# light.net
KiCad netlist of a schematic drawn in Altium Designer
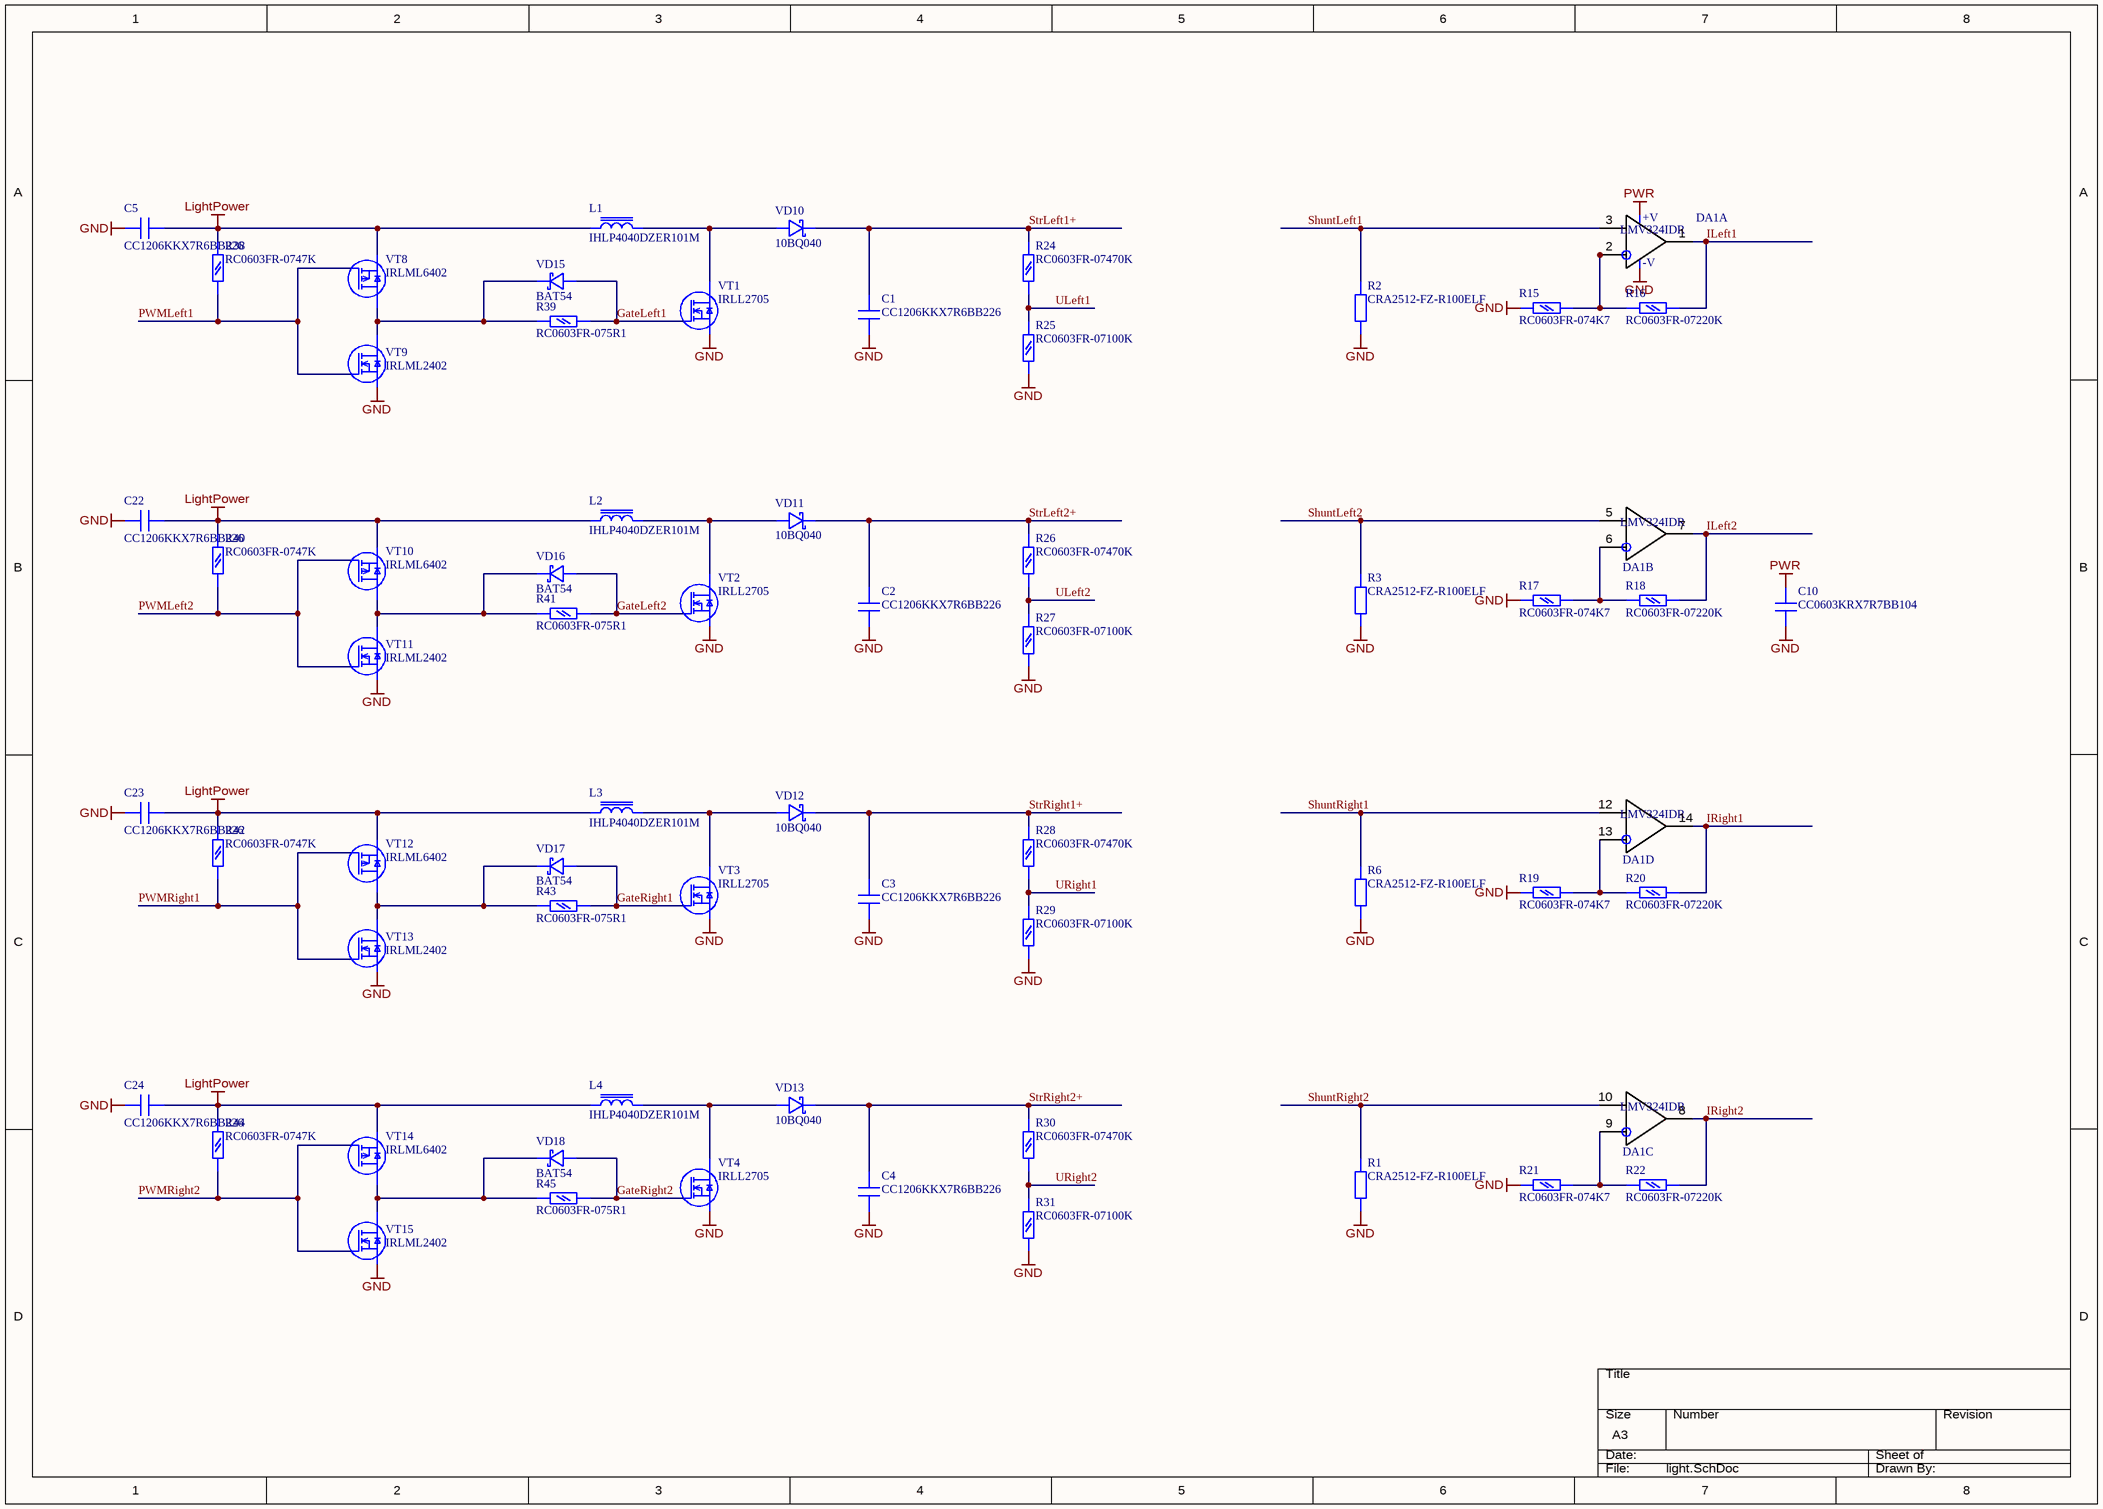
[diagram p0: light.SchDoc]

(export (version "E")
  (design (tool "Eeschema 10.0.6"))
  (components
    (comp (ref "C1")
      (value "CC1206KKX7R6BB226")
      (footprint "CapacitorSMD1206(reflow)")
      (description "CAPACITOR Capacitor SMD 1206 3.2x1.6mm")
      (libsource (lib "Integrated_Library") (part "CapacitorSMD1206(reflow)"))
    )
    (comp (ref "C2")
      (value "CC1206KKX7R6BB226")
      (footprint "CapacitorSMD1206(reflow)")
      (description "CAPACITOR Capacitor SMD 1206 3.2x1.6mm")
      (libsource (lib "Integrated_Library") (part "CapacitorSMD1206(reflow)"))
    )
    (comp (ref "C3")
      (value "CC1206KKX7R6BB226")
      (footprint "CapacitorSMD1206(reflow)")
      (description "CAPACITOR Capacitor SMD 1206 3.2x1.6mm")
      (libsource (lib "Integrated_Library") (part "CapacitorSMD1206(reflow)"))
    )
    (comp (ref "C4")
      (value "CC1206KKX7R6BB226")
      (footprint "CapacitorSMD1206(reflow)")
      (description "CAPACITOR Capacitor SMD 1206 3.2x1.6mm")
      (libsource (lib "Integrated_Library") (part "CapacitorSMD1206(reflow)"))
    )
    (comp (ref "C5")
      (value "CC1206KKX7R6BB226")
      (footprint "CapacitorSMD1206(reflow)")
      (description "CAPACITOR Capacitor SMD 1206 3.2x1.6mm")
      (libsource (lib "Integrated_Library") (part "CapacitorSMD1206(reflow)"))
    )
    (comp (ref "C10")
      (value "CC0603KRX7R7BB104")
      (footprint "CapacitorSMD0603(manual)")
      (description "CAPACITOR Capacitor SMD 0603 1.6x0.8mm")
      (libsource (lib "Integrated_Library") (part "CapacitorSMD0603(reflow)"))
    )
    (comp (ref "C22")
      (value "CC1206KKX7R6BB226")
      (footprint "CapacitorSMD1206(reflow)")
      (description "CAPACITOR Capacitor SMD 1206 3.2x1.6mm")
      (libsource (lib "Integrated_Library") (part "CapacitorSMD1206(reflow)"))
    )
    (comp (ref "C23")
      (value "CC1206KKX7R6BB226")
      (footprint "CapacitorSMD1206(reflow)")
      (description "CAPACITOR Capacitor SMD 1206 3.2x1.6mm")
      (libsource (lib "Integrated_Library") (part "CapacitorSMD1206(reflow)"))
    )
    (comp (ref "C24")
      (value "CC1206KKX7R6BB226")
      (footprint "CapacitorSMD1206(reflow)")
      (description "CAPACITOR Capacitor SMD 1206 3.2x1.6mm")
      (libsource (lib "Integrated_Library") (part "CapacitorSMD1206(reflow)"))
    )
    (comp (ref "DA1")
      (value "LMV324IDR")
      (footprint "SO14")
      (description "IC generic quad op amp SO14")
      (libsource (lib "Integrated_Library") (part "OpAmp_Quad_SO14"))
    )
    (comp (ref "L1")
      (value "IHLP4040DZER101M")
      (footprint "IHLP-4040DZ(manual/deep1.5mm)")
      (description "MAGNETIC Inductor SMD 4040 h=4mm")
      (libsource (lib "Integrated_Library") (part "IHLP-4040DZ"))
    )
    (comp (ref "L2")
      (value "IHLP4040DZER101M")
      (footprint "IHLP-4040DZ(manual/deep1.5mm)")
      (description "MAGNETIC Inductor SMD 4040 h=4mm")
      (libsource (lib "Integrated_Library") (part "IHLP-4040DZ"))
    )
    (comp (ref "L3")
      (value "IHLP4040DZER101M")
      (footprint "IHLP-4040DZ(manual/deep1.5mm)")
      (description "MAGNETIC Inductor SMD 4040 h=4mm")
      (libsource (lib "Integrated_Library") (part "IHLP-4040DZ"))
    )
    (comp (ref "L4")
      (value "IHLP4040DZER101M")
      (footprint "IHLP-4040DZ(manual/deep1.5mm)")
      (description "MAGNETIC Inductor SMD 4040 h=4mm")
      (libsource (lib "Integrated_Library") (part "IHLP-4040DZ"))
    )
    (comp (ref "R1")
      (value "CRA2512-FZ-R100ELF")
      (footprint "ResistorSMD2512(reflow)")
      (description "RESISTOR Resistor SMD 2512 6.35x3.2mm")
      (libsource (lib "Integrated_Library") (part "ResistorSMD2512(reflow)"))
    )
    (comp (ref "R2")
      (value "CRA2512-FZ-R100ELF")
      (footprint "ResistorSMD2512(reflow)")
      (description "RESISTOR Resistor SMD 2512 6.35x3.2mm")
      (libsource (lib "Integrated_Library") (part "ResistorSMD2512(reflow)"))
    )
    (comp (ref "R3")
      (value "CRA2512-FZ-R100ELF")
      (footprint "ResistorSMD2512(reflow)")
      (description "RESISTOR Resistor SMD 2512 6.35x3.2mm")
      (libsource (lib "Integrated_Library") (part "ResistorSMD2512(reflow)"))
    )
    (comp (ref "R6")
      (value "CRA2512-FZ-R100ELF")
      (footprint "ResistorSMD2512(reflow)")
      (description "RESISTOR Resistor SMD 2512 6.35x3.2mm")
      (libsource (lib "Integrated_Library") (part "ResistorSMD2512(reflow)"))
    )
    (comp (ref "R15")
      (value "RC0603FR-074K7")
      (footprint "ResistorSMD0603(manual)")
      (description "RESISTOR Resistor SMD 0603 1.6x0.8mm")
      (libsource (lib "Integrated_Library") (part "ResistorSMD0603(reflow)"))
    )
    (comp (ref "R16")
      (value "RC0603FR-07220K")
      (footprint "ResistorSMD0603(manual)")
      (description "RESISTOR Resistor SMD 0603 1.6x0.8mm")
      (libsource (lib "Integrated_Library") (part "ResistorSMD0603(reflow)"))
    )
    (comp (ref "R17")
      (value "RC0603FR-074K7")
      (footprint "ResistorSMD0603(manual)")
      (description "RESISTOR Resistor SMD 0603 1.6x0.8mm")
      (libsource (lib "Integrated_Library") (part "ResistorSMD0603(reflow)"))
    )
    (comp (ref "R18")
      (value "RC0603FR-07220K")
      (footprint "ResistorSMD0603(manual)")
      (description "RESISTOR Resistor SMD 0603 1.6x0.8mm")
      (libsource (lib "Integrated_Library") (part "ResistorSMD0603(reflow)"))
    )
    (comp (ref "R19")
      (value "RC0603FR-074K7")
      (footprint "ResistorSMD0603(manual)")
      (description "RESISTOR Resistor SMD 0603 1.6x0.8mm")
      (libsource (lib "Integrated_Library") (part "ResistorSMD0603(reflow)"))
    )
    (comp (ref "R20")
      (value "RC0603FR-07220K")
      (footprint "ResistorSMD0603(manual)")
      (description "RESISTOR Resistor SMD 0603 1.6x0.8mm")
      (libsource (lib "Integrated_Library") (part "ResistorSMD0603(reflow)"))
    )
    (comp (ref "R21")
      (value "RC0603FR-074K7")
      (footprint "ResistorSMD0603(manual)")
      (description "RESISTOR Resistor SMD 0603 1.6x0.8mm")
      (libsource (lib "Integrated_Library") (part "ResistorSMD0603(reflow)"))
    )
    (comp (ref "R22")
      (value "RC0603FR-07220K")
      (footprint "ResistorSMD0603(manual)")
      (description "RESISTOR Resistor SMD 0603 1.6x0.8mm")
      (libsource (lib "Integrated_Library") (part "ResistorSMD0603(reflow)"))
    )
    (comp (ref "R24")
      (value "RC0603FR-07470K")
      (footprint "ResistorSMD0603(manual)")
      (description "RESISTOR Resistor SMD 0603 1.6x0.8mm")
      (libsource (lib "Integrated_Library") (part "ResistorSMD0603(reflow)"))
    )
    (comp (ref "R25")
      (value "RC0603FR-07100K")
      (footprint "ResistorSMD0603(manual)")
      (description "RESISTOR Resistor SMD 0603 1.6x0.8mm")
      (libsource (lib "Integrated_Library") (part "ResistorSMD0603(reflow)"))
    )
    (comp (ref "R26")
      (value "RC0603FR-07470K")
      (footprint "ResistorSMD0603(manual)")
      (description "RESISTOR Resistor SMD 0603 1.6x0.8mm")
      (libsource (lib "Integrated_Library") (part "ResistorSMD0603(reflow)"))
    )
    (comp (ref "R27")
      (value "RC0603FR-07100K")
      (footprint "ResistorSMD0603(manual)")
      (description "RESISTOR Resistor SMD 0603 1.6x0.8mm")
      (libsource (lib "Integrated_Library") (part "ResistorSMD0603(reflow)"))
    )
    (comp (ref "R28")
      (value "RC0603FR-07470K")
      (footprint "ResistorSMD0603(manual)")
      (description "RESISTOR Resistor SMD 0603 1.6x0.8mm")
      (libsource (lib "Integrated_Library") (part "ResistorSMD0603(reflow)"))
    )
    (comp (ref "R29")
      (value "RC0603FR-07100K")
      (footprint "ResistorSMD0603(manual)")
      (description "RESISTOR Resistor SMD 0603 1.6x0.8mm")
      (libsource (lib "Integrated_Library") (part "ResistorSMD0603(reflow)"))
    )
    (comp (ref "R30")
      (value "RC0603FR-07470K")
      (footprint "ResistorSMD0603(manual)")
      (description "RESISTOR Resistor SMD 0603 1.6x0.8mm")
      (libsource (lib "Integrated_Library") (part "ResistorSMD0603(reflow)"))
    )
    (comp (ref "R31")
      (value "RC0603FR-07100K")
      (footprint "ResistorSMD0603(manual)")
      (description "RESISTOR Resistor SMD 0603 1.6x0.8mm")
      (libsource (lib "Integrated_Library") (part "ResistorSMD0603(reflow)"))
    )
    (comp (ref "R38")
      (value "RC0603FR-0747K")
      (footprint "ResistorSMD0603(manual)")
      (description "RESISTOR Resistor SMD 0603 1.6x0.8mm")
      (libsource (lib "Integrated_Library") (part "ResistorSMD0603(reflow)"))
    )
    (comp (ref "R39")
      (value "RC0603FR-075R1")
      (footprint "ResistorSMD0603(manual)")
      (description "RESISTOR Resistor SMD 0603 1.6x0.8mm")
      (libsource (lib "Integrated_Library") (part "ResistorSMD0603(reflow)"))
    )
    (comp (ref "R40")
      (value "RC0603FR-0747K")
      (footprint "ResistorSMD0603(manual)")
      (description "RESISTOR Resistor SMD 0603 1.6x0.8mm")
      (libsource (lib "Integrated_Library") (part "ResistorSMD0603(reflow)"))
    )
    (comp (ref "R41")
      (value "RC0603FR-075R1")
      (footprint "ResistorSMD0603(manual)")
      (description "RESISTOR Resistor SMD 0603 1.6x0.8mm")
      (libsource (lib "Integrated_Library") (part "ResistorSMD0603(reflow)"))
    )
    (comp (ref "R42")
      (value "RC0603FR-0747K")
      (footprint "ResistorSMD0603(manual)")
      (description "RESISTOR Resistor SMD 0603 1.6x0.8mm")
      (libsource (lib "Integrated_Library") (part "ResistorSMD0603(reflow)"))
    )
    (comp (ref "R43")
      (value "RC0603FR-075R1")
      (footprint "ResistorSMD0603(manual)")
      (description "RESISTOR Resistor SMD 0603 1.6x0.8mm")
      (libsource (lib "Integrated_Library") (part "ResistorSMD0603(reflow)"))
    )
    (comp (ref "R44")
      (value "RC0603FR-0747K")
      (footprint "ResistorSMD0603(manual)")
      (description "RESISTOR Resistor SMD 0603 1.6x0.8mm")
      (libsource (lib "Integrated_Library") (part "ResistorSMD0603(reflow)"))
    )
    (comp (ref "R45")
      (value "RC0603FR-075R1")
      (footprint "ResistorSMD0603(manual)")
      (description "RESISTOR Resistor SMD 0603 1.6x0.8mm")
      (libsource (lib "Integrated_Library") (part "ResistorSMD0603(reflow)"))
    )
    (comp (ref "VD10")
      (value "10BQ040")
      (footprint "SMB_10BQ40")
      (description "DIODE Schottky rectifier")
      (libsource (lib "Integrated_Library") (part "10BQ___"))
    )
    (comp (ref "VD11")
      (value "10BQ040")
      (footprint "SMB_10BQ40")
      (description "DIODE Schottky rectifier")
      (libsource (lib "Integrated_Library") (part "10BQ___"))
    )
    (comp (ref "VD12")
      (value "10BQ040")
      (footprint "SMB_10BQ40")
      (description "DIODE Schottky rectifier")
      (libsource (lib "Integrated_Library") (part "10BQ___"))
    )
    (comp (ref "VD13")
      (value "10BQ040")
      (footprint "SMB_10BQ40")
      (description "DIODE Schottky rectifier")
      (libsource (lib "Integrated_Library") (part "10BQ___"))
    )
    (comp (ref "VD15")
      (value "BAT54")
      (footprint "SOT23")
      (description "DIODE Schottky barrier diodes")
      (libsource (lib "Integrated_Library") (part "BAT54"))
    )
    (comp (ref "VD16")
      (value "BAT54")
      (footprint "SOT23")
      (description "DIODE Schottky barrier diodes")
      (libsource (lib "Integrated_Library") (part "BAT54"))
    )
    (comp (ref "VD17")
      (value "BAT54")
      (footprint "SOT23")
      (description "DIODE Schottky barrier diodes")
      (libsource (lib "Integrated_Library") (part "BAT54"))
    )
    (comp (ref "VD18")
      (value "BAT54")
      (footprint "SOT23")
      (description "DIODE Schottky barrier diodes")
      (libsource (lib "Integrated_Library") (part "BAT54"))
    )
    (comp (ref "VT1")
      (value "IRLL2705")
      (footprint "SOT223")
      (description "TRANSISTOR MOSFET N generic sot23")
      (libsource (lib "Integrated_Library") (part "MOSFET_N_SOT223"))
    )
    (comp (ref "VT2")
      (value "IRLL2705")
      (footprint "SOT223")
      (description "TRANSISTOR MOSFET N generic sot23")
      (libsource (lib "Integrated_Library") (part "MOSFET_N_SOT223"))
    )
    (comp (ref "VT3")
      (value "IRLL2705")
      (footprint "SOT223")
      (description "TRANSISTOR MOSFET N generic sot23")
      (libsource (lib "Integrated_Library") (part "MOSFET_N_SOT223"))
    )
    (comp (ref "VT4")
      (value "IRLL2705")
      (footprint "SOT223")
      (description "TRANSISTOR MOSFET N generic sot23")
      (libsource (lib "Integrated_Library") (part "MOSFET_N_SOT223"))
    )
    (comp (ref "VT8")
      (value "IRLML6402")
      (footprint "SOT23")
      (description "TRANSISTOR MOSFET P generic sot23")
      (libsource (lib "Integrated_Library") (part "MOSFET_P_sot23"))
    )
    (comp (ref "VT9")
      (value "IRLML2402")
      (footprint "SOT23")
      (description "TRANSISTOR MOSFET N generic sot23")
      (libsource (lib "Integrated_Library") (part "MOSFET_N_sot23"))
    )
    (comp (ref "VT10")
      (value "IRLML6402")
      (footprint "SOT23")
      (description "TRANSISTOR MOSFET P generic sot23")
      (libsource (lib "Integrated_Library") (part "MOSFET_P_sot23"))
    )
    (comp (ref "VT11")
      (value "IRLML2402")
      (footprint "SOT23")
      (description "TRANSISTOR MOSFET N generic sot23")
      (libsource (lib "Integrated_Library") (part "MOSFET_N_sot23"))
    )
    (comp (ref "VT12")
      (value "IRLML6402")
      (footprint "SOT23")
      (description "TRANSISTOR MOSFET P generic sot23")
      (libsource (lib "Integrated_Library") (part "MOSFET_P_sot23"))
    )
    (comp (ref "VT13")
      (value "IRLML2402")
      (footprint "SOT23")
      (description "TRANSISTOR MOSFET N generic sot23")
      (libsource (lib "Integrated_Library") (part "MOSFET_N_sot23"))
    )
    (comp (ref "VT14")
      (value "IRLML6402")
      (footprint "SOT23")
      (description "TRANSISTOR MOSFET P generic sot23")
      (libsource (lib "Integrated_Library") (part "MOSFET_P_sot23"))
    )
    (comp (ref "VT15")
      (value "IRLML2402")
      (footprint "SOT23")
      (description "TRANSISTOR MOSFET N generic sot23")
      (libsource (lib "Integrated_Library") (part "MOSFET_N_sot23"))
    )
  )
  (nets
    (net (code "1") (name "/GateLeft1") (class "Default")
      (node (ref "R39") (pin "1") (pinfunction "1_1") (pintype "passive"))
      (node (ref "VD15") (pin "1") (pintype "passive"))
      (node (ref "VT1") (pin "1") (pinfunction "G_1") (pintype "passive"))
    )
    (net (code "2") (name "/GateLeft2") (class "Default")
      (node (ref "R41") (pin "1") (pinfunction "1_1") (pintype "passive"))
      (node (ref "VD16") (pin "1") (pintype "passive"))
      (node (ref "VT2") (pin "1") (pinfunction "G_1") (pintype "passive"))
    )
    (net (code "3") (name "/GateRight1") (class "Default")
      (node (ref "R43") (pin "1") (pinfunction "1_1") (pintype "passive"))
      (node (ref "VD17") (pin "1") (pintype "passive"))
      (node (ref "VT3") (pin "1") (pinfunction "G_1") (pintype "passive"))
    )
    (net (code "4") (name "/GateRight2") (class "Default")
      (node (ref "R45") (pin "1") (pinfunction "1_1") (pintype "passive"))
      (node (ref "VD18") (pin "1") (pintype "passive"))
      (node (ref "VT4") (pin "1") (pinfunction "G_1") (pintype "passive"))
    )
    (net (code "5") (name "/ILeft1") (class "Default")
      (node (ref "DA1") (pin "1") (pinfunction "1_1") (pintype "passive"))
      (node (ref "R16") (pin "2") (pinfunction "2_2") (pintype "passive"))
    )
    (net (code "6") (name "/ILeft2") (class "Default")
      (node (ref "DA1") (pin "7") (pinfunction "7_7") (pintype "passive"))
      (node (ref "R18") (pin "2") (pinfunction "2_2") (pintype "passive"))
    )
    (net (code "7") (name "/IRight1") (class "Default")
      (node (ref "DA1") (pin "14") (pinfunction "14_14") (pintype "passive"))
      (node (ref "R20") (pin "2") (pinfunction "2_2") (pintype "passive"))
    )
    (net (code "8") (name "/IRight2") (class "Default")
      (node (ref "DA1") (pin "8") (pinfunction "8_8") (pintype "passive"))
      (node (ref "R22") (pin "2") (pinfunction "2_2") (pintype "passive"))
    )
    (net (code "9") (name "/PWMLeft1") (class "Default")
      (node (ref "R38") (pin "2") (pinfunction "2_2") (pintype "passive"))
      (node (ref "VT8") (pin "1") (pinfunction "G_1") (pintype "passive"))
      (node (ref "VT9") (pin "1") (pinfunction "G_1") (pintype "passive"))
    )
    (net (code "10") (name "/PWMLeft2") (class "Default")
      (node (ref "R40") (pin "2") (pinfunction "2_2") (pintype "passive"))
      (node (ref "VT10") (pin "1") (pinfunction "G_1") (pintype "passive"))
      (node (ref "VT11") (pin "1") (pinfunction "G_1") (pintype "passive"))
    )
    (net (code "11") (name "/PWMRight1") (class "Default")
      (node (ref "R42") (pin "2") (pinfunction "2_2") (pintype "passive"))
      (node (ref "VT12") (pin "1") (pinfunction "G_1") (pintype "passive"))
      (node (ref "VT13") (pin "1") (pinfunction "G_1") (pintype "passive"))
    )
    (net (code "12") (name "/PWMRight2") (class "Default")
      (node (ref "R44") (pin "2") (pinfunction "2_2") (pintype "passive"))
      (node (ref "VT14") (pin "1") (pinfunction "G_1") (pintype "passive"))
      (node (ref "VT15") (pin "1") (pinfunction "G_1") (pintype "passive"))
    )
    (net (code "13") (name "/ShuntLeft1") (class "Default")
      (node (ref "DA1") (pin "3") (pinfunction "3_3") (pintype "passive"))
      (node (ref "R2") (pin "2") (pinfunction "2_2") (pintype "passive"))
    )
    (net (code "14") (name "/ShuntLeft2") (class "Default")
      (node (ref "DA1") (pin "5") (pinfunction "5_5") (pintype "passive"))
      (node (ref "R3") (pin "2") (pinfunction "2_2") (pintype "passive"))
    )
    (net (code "15") (name "/ShuntRight1") (class "Default")
      (node (ref "DA1") (pin "12") (pinfunction "12_12") (pintype "passive"))
      (node (ref "R6") (pin "2") (pinfunction "2_2") (pintype "passive"))
    )
    (net (code "16") (name "/ShuntRight2") (class "Default")
      (node (ref "DA1") (pin "10") (pinfunction "10_10") (pintype "passive"))
      (node (ref "R1") (pin "2") (pinfunction "2_2") (pintype "passive"))
    )
    (net (code "17") (name "/StrLeft1+") (class "Default")
      (node (ref "C1") (pin "2") (pintype "passive"))
      (node (ref "R24") (pin "2") (pinfunction "2_2") (pintype "passive"))
      (node (ref "VD10") (pin "2") (pintype "passive"))
    )
    (net (code "18") (name "/StrLeft2+") (class "Default")
      (node (ref "C2") (pin "2") (pintype "passive"))
      (node (ref "R26") (pin "2") (pinfunction "2_2") (pintype "passive"))
      (node (ref "VD11") (pin "2") (pintype "passive"))
    )
    (net (code "19") (name "/StrRight1+") (class "Default")
      (node (ref "C3") (pin "2") (pintype "passive"))
      (node (ref "R28") (pin "2") (pinfunction "2_2") (pintype "passive"))
      (node (ref "VD12") (pin "2") (pintype "passive"))
    )
    (net (code "20") (name "/StrRight2+") (class "Default")
      (node (ref "C4") (pin "2") (pintype "passive"))
      (node (ref "R30") (pin "2") (pinfunction "2_2") (pintype "passive"))
      (node (ref "VD13") (pin "2") (pintype "passive"))
    )
    (net (code "21") (name "/ULeft1") (class "Default")
      (node (ref "R24") (pin "1") (pinfunction "1_1") (pintype "passive"))
      (node (ref "R25") (pin "2") (pinfunction "2_2") (pintype "passive"))
    )
    (net (code "22") (name "/ULeft2") (class "Default")
      (node (ref "R26") (pin "1") (pinfunction "1_1") (pintype "passive"))
      (node (ref "R27") (pin "2") (pinfunction "2_2") (pintype "passive"))
    )
    (net (code "23") (name "/URight1") (class "Default")
      (node (ref "R28") (pin "1") (pinfunction "1_1") (pintype "passive"))
      (node (ref "R29") (pin "2") (pinfunction "2_2") (pintype "passive"))
    )
    (net (code "24") (name "/URight2") (class "Default")
      (node (ref "R30") (pin "1") (pinfunction "1_1") (pintype "passive"))
      (node (ref "R31") (pin "2") (pinfunction "2_2") (pintype "passive"))
    )
    (net (code "25") (name "GND") (class "Default")
      (node (ref "C1") (pin "1") (pintype "passive"))
      (node (ref "C10") (pin "1") (pintype "passive"))
      (node (ref "C2") (pin "1") (pintype "passive"))
      (node (ref "C22") (pin "2") (pintype "passive"))
      (node (ref "C23") (pin "2") (pintype "passive"))
      (node (ref "C24") (pin "2") (pintype "passive"))
      (node (ref "C3") (pin "1") (pintype "passive"))
      (node (ref "C4") (pin "1") (pintype "passive"))
      (node (ref "C5") (pin "2") (pintype "passive"))
      (node (ref "DA1") (pin "11") (pinfunction "11_11") (pintype "passive"))
      (node (ref "R1") (pin "1") (pinfunction "1_1") (pintype "passive"))
      (node (ref "R15") (pin "1") (pinfunction "1_1") (pintype "passive"))
      (node (ref "R17") (pin "1") (pinfunction "1_1") (pintype "passive"))
      (node (ref "R19") (pin "1") (pinfunction "1_1") (pintype "passive"))
      (node (ref "R2") (pin "1") (pinfunction "1_1") (pintype "passive"))
      (node (ref "R21") (pin "1") (pinfunction "1_1") (pintype "passive"))
      (node (ref "R25") (pin "1") (pinfunction "1_1") (pintype "passive"))
      (node (ref "R27") (pin "1") (pinfunction "1_1") (pintype "passive"))
      (node (ref "R29") (pin "1") (pinfunction "1_1") (pintype "passive"))
      (node (ref "R3") (pin "1") (pinfunction "1_1") (pintype "passive"))
      (node (ref "R31") (pin "1") (pinfunction "1_1") (pintype "passive"))
      (node (ref "R6") (pin "1") (pinfunction "1_1") (pintype "passive"))
      (node (ref "VT1") (pin "3") (pinfunction "S_3") (pintype "passive"))
      (node (ref "VT11") (pin "2") (pinfunction "S_2") (pintype "passive"))
      (node (ref "VT13") (pin "2") (pinfunction "S_2") (pintype "passive"))
      (node (ref "VT15") (pin "2") (pinfunction "S_2") (pintype "passive"))
      (node (ref "VT2") (pin "3") (pinfunction "S_3") (pintype "passive"))
      (node (ref "VT3") (pin "3") (pinfunction "S_3") (pintype "passive"))
      (node (ref "VT4") (pin "3") (pinfunction "S_3") (pintype "passive"))
      (node (ref "VT9") (pin "2") (pinfunction "S_2") (pintype "passive"))
    )
    (net (code "26") (name "LightPower") (class "Default")
      (node (ref "C22") (pin "1") (pintype "passive"))
      (node (ref "C23") (pin "1") (pintype "passive"))
      (node (ref "C24") (pin "1") (pintype "passive"))
      (node (ref "C5") (pin "1") (pintype "passive"))
      (node (ref "L1") (pin "1") (pintype "passive"))
      (node (ref "L2") (pin "1") (pintype "passive"))
      (node (ref "L3") (pin "1") (pintype "passive"))
      (node (ref "L4") (pin "1") (pintype "passive"))
      (node (ref "R38") (pin "1") (pinfunction "1_1") (pintype "passive"))
      (node (ref "R40") (pin "1") (pinfunction "1_1") (pintype "passive"))
      (node (ref "R42") (pin "1") (pinfunction "1_1") (pintype "passive"))
      (node (ref "R44") (pin "1") (pinfunction "1_1") (pintype "passive"))
      (node (ref "VT10") (pin "2") (pinfunction "S_2") (pintype "passive"))
      (node (ref "VT12") (pin "2") (pinfunction "S_2") (pintype "passive"))
      (node (ref "VT14") (pin "2") (pinfunction "S_2") (pintype "passive"))
      (node (ref "VT8") (pin "2") (pinfunction "S_2") (pintype "passive"))
    )
    (net (code "27") (name "Net-(DA1-Pad2)") (class "Default")
      (node (ref "DA1") (pin "2") (pinfunction "2_2") (pintype "passive"))
      (node (ref "R15") (pin "2") (pinfunction "2_2") (pintype "passive"))
      (node (ref "R16") (pin "1") (pinfunction "1_1") (pintype "passive"))
    )
    (net (code "28") (name "Net-(DA1-Pad6)") (class "Default")
      (node (ref "DA1") (pin "6") (pinfunction "6_6") (pintype "passive"))
      (node (ref "R17") (pin "2") (pinfunction "2_2") (pintype "passive"))
      (node (ref "R18") (pin "1") (pinfunction "1_1") (pintype "passive"))
    )
    (net (code "29") (name "Net-(DA1-Pad9)") (class "Default")
      (node (ref "DA1") (pin "9") (pinfunction "9_9") (pintype "passive"))
      (node (ref "R21") (pin "2") (pinfunction "2_2") (pintype "passive"))
      (node (ref "R22") (pin "1") (pinfunction "1_1") (pintype "passive"))
    )
    (net (code "30") (name "Net-(DA1-Pad13)") (class "Default")
      (node (ref "DA1") (pin "13") (pinfunction "13_13") (pintype "passive"))
      (node (ref "R19") (pin "2") (pinfunction "2_2") (pintype "passive"))
      (node (ref "R20") (pin "1") (pinfunction "1_1") (pintype "passive"))
    )
    (net (code "31") (name "Net-(VT1-D)") (class "Default")
      (node (ref "L1") (pin "2") (pintype "passive"))
      (node (ref "VD10") (pin "1") (pintype "passive"))
      (node (ref "VT1") (pin "2") (pinfunction "D_2") (pintype "passive"))
    )
    (net (code "32") (name "Net-(VT2-D)") (class "Default")
      (node (ref "L2") (pin "2") (pintype "passive"))
      (node (ref "VD11") (pin "1") (pintype "passive"))
      (node (ref "VT2") (pin "2") (pinfunction "D_2") (pintype "passive"))
    )
    (net (code "33") (name "Net-(VT3-D)") (class "Default")
      (node (ref "L3") (pin "2") (pintype "passive"))
      (node (ref "VD12") (pin "1") (pintype "passive"))
      (node (ref "VT3") (pin "2") (pinfunction "D_2") (pintype "passive"))
    )
    (net (code "34") (name "Net-(VT4-D)") (class "Default")
      (node (ref "L4") (pin "2") (pintype "passive"))
      (node (ref "VD13") (pin "1") (pintype "passive"))
      (node (ref "VT4") (pin "2") (pinfunction "D_2") (pintype "passive"))
    )
    (net (code "35") (name "Net-(VT8-D)") (class "Default")
      (node (ref "R39") (pin "2") (pinfunction "2_2") (pintype "passive"))
      (node (ref "VD15") (pin "3") (pintype "passive"))
      (node (ref "VT8") (pin "3") (pinfunction "D_3") (pintype "passive"))
      (node (ref "VT9") (pin "3") (pinfunction "D_3") (pintype "passive"))
    )
    (net (code "36") (name "Net-(VT10-D)") (class "Default")
      (node (ref "R41") (pin "2") (pinfunction "2_2") (pintype "passive"))
      (node (ref "VD16") (pin "3") (pintype "passive"))
      (node (ref "VT10") (pin "3") (pinfunction "D_3") (pintype "passive"))
      (node (ref "VT11") (pin "3") (pinfunction "D_3") (pintype "passive"))
    )
    (net (code "37") (name "Net-(VT12-D)") (class "Default")
      (node (ref "R43") (pin "2") (pinfunction "2_2") (pintype "passive"))
      (node (ref "VD17") (pin "3") (pintype "passive"))
      (node (ref "VT12") (pin "3") (pinfunction "D_3") (pintype "passive"))
      (node (ref "VT13") (pin "3") (pinfunction "D_3") (pintype "passive"))
    )
    (net (code "38") (name "Net-(VT14-D)") (class "Default")
      (node (ref "R45") (pin "2") (pinfunction "2_2") (pintype "passive"))
      (node (ref "VD18") (pin "3") (pintype "passive"))
      (node (ref "VT14") (pin "3") (pinfunction "D_3") (pintype "passive"))
      (node (ref "VT15") (pin "3") (pinfunction "D_3") (pintype "passive"))
    )
    (net (code "39") (name "PWR") (class "Default")
      (node (ref "C10") (pin "2") (pintype "passive"))
      (node (ref "DA1") (pin "4") (pinfunction "4_4") (pintype "passive"))
    )
  )
)
